# Vending.net
KiCad netlist of a schematic drawn in EAGLE
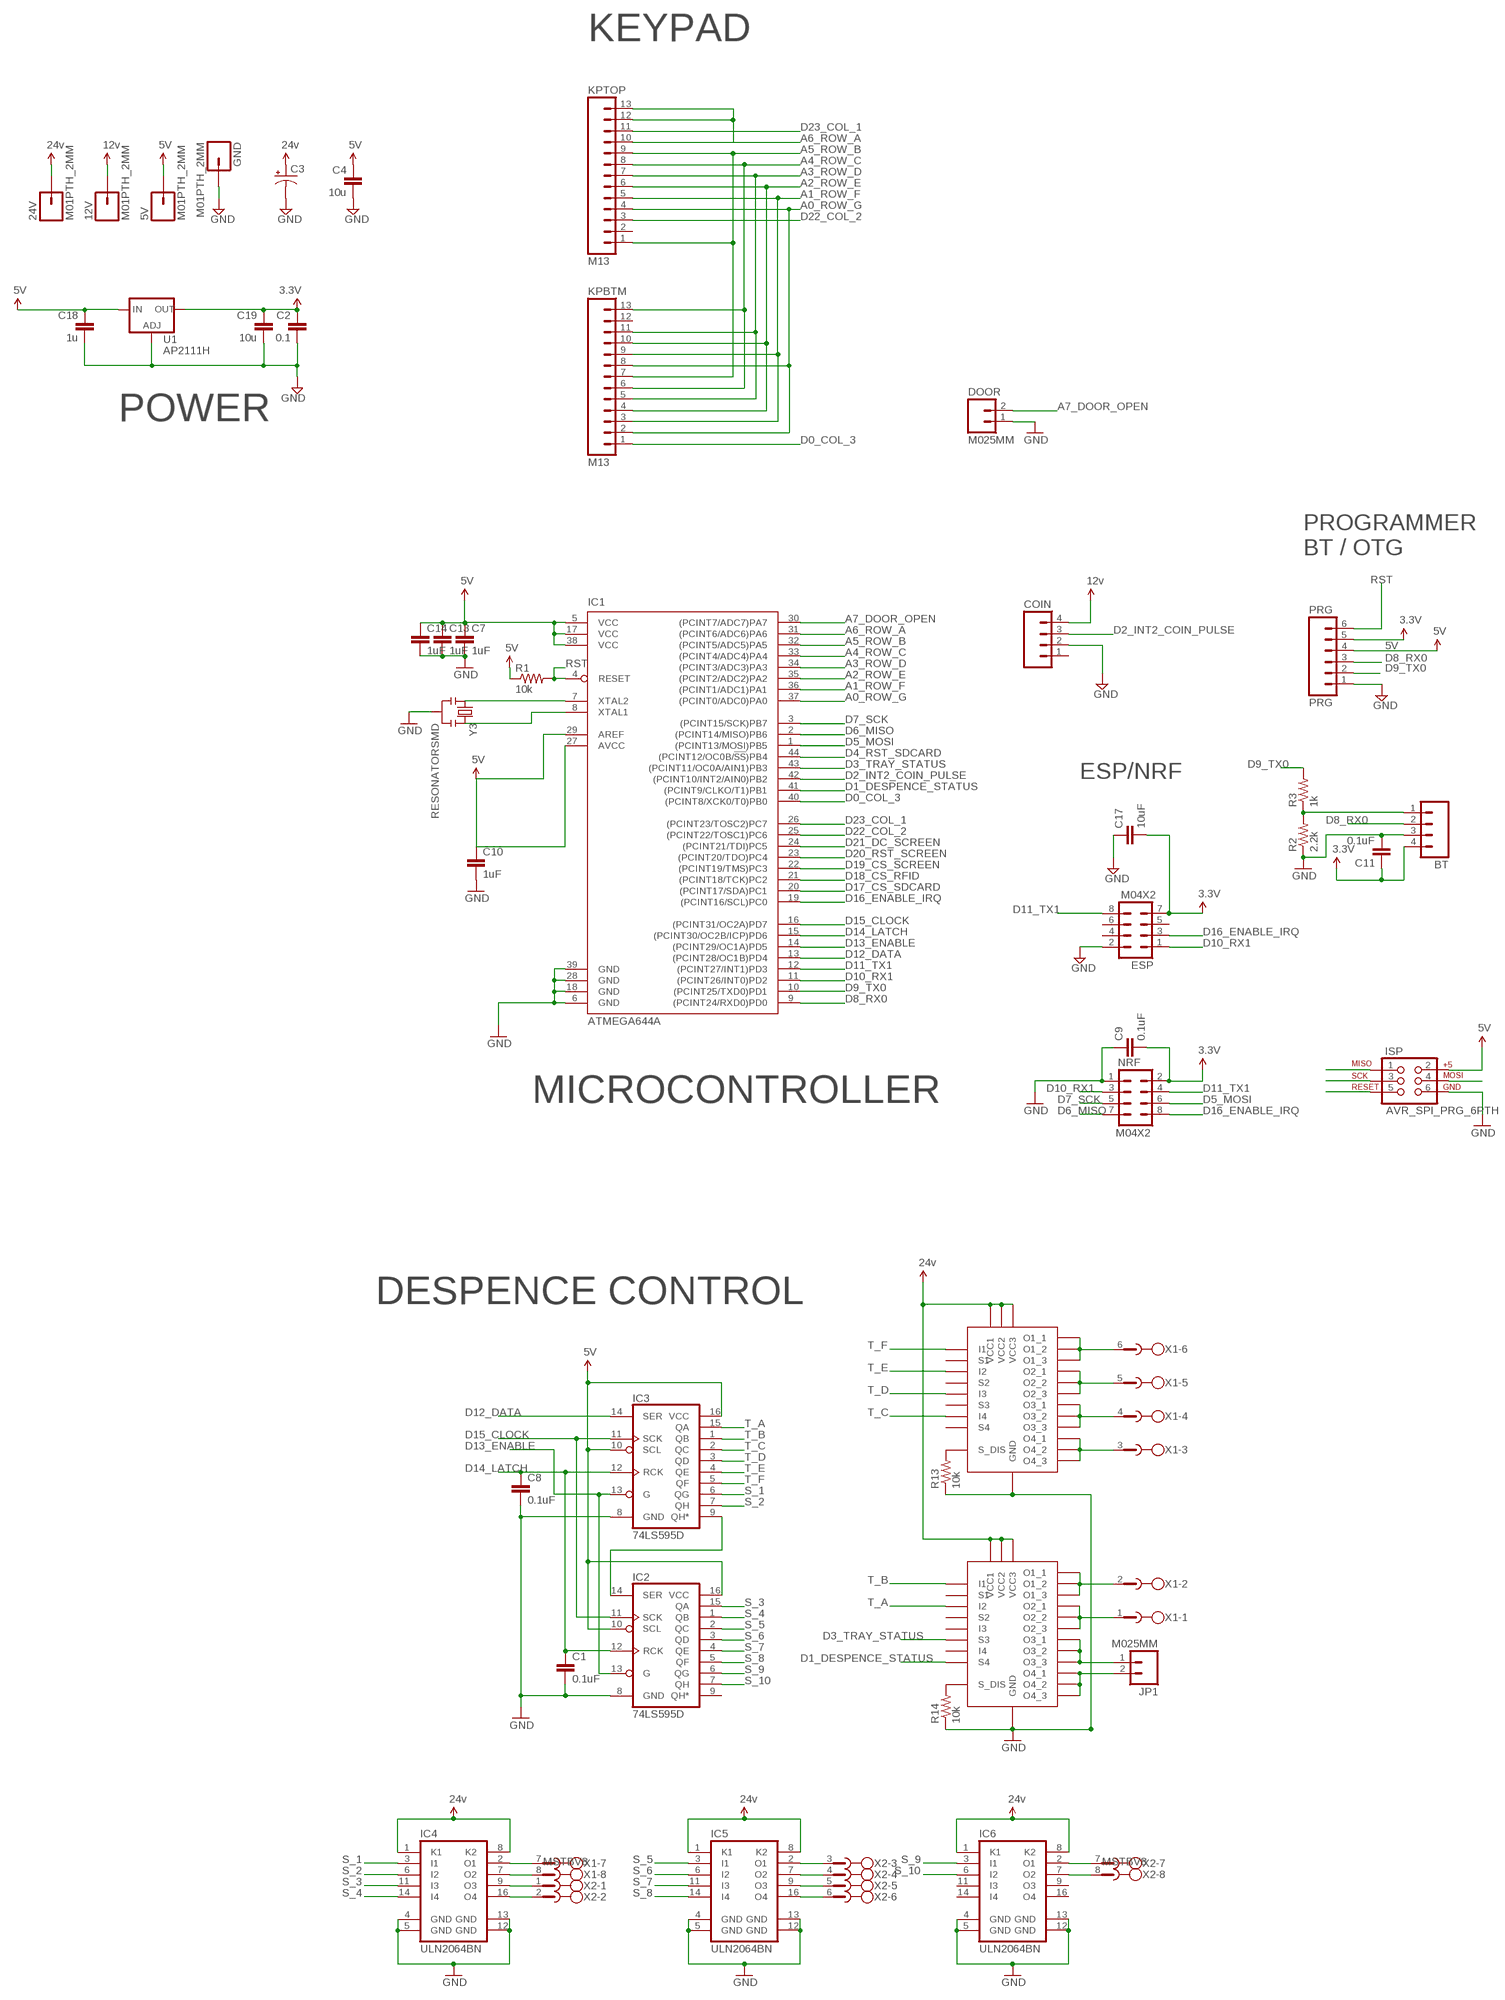
[diagram p0: schematic, sheet 1, part 1 of 2]
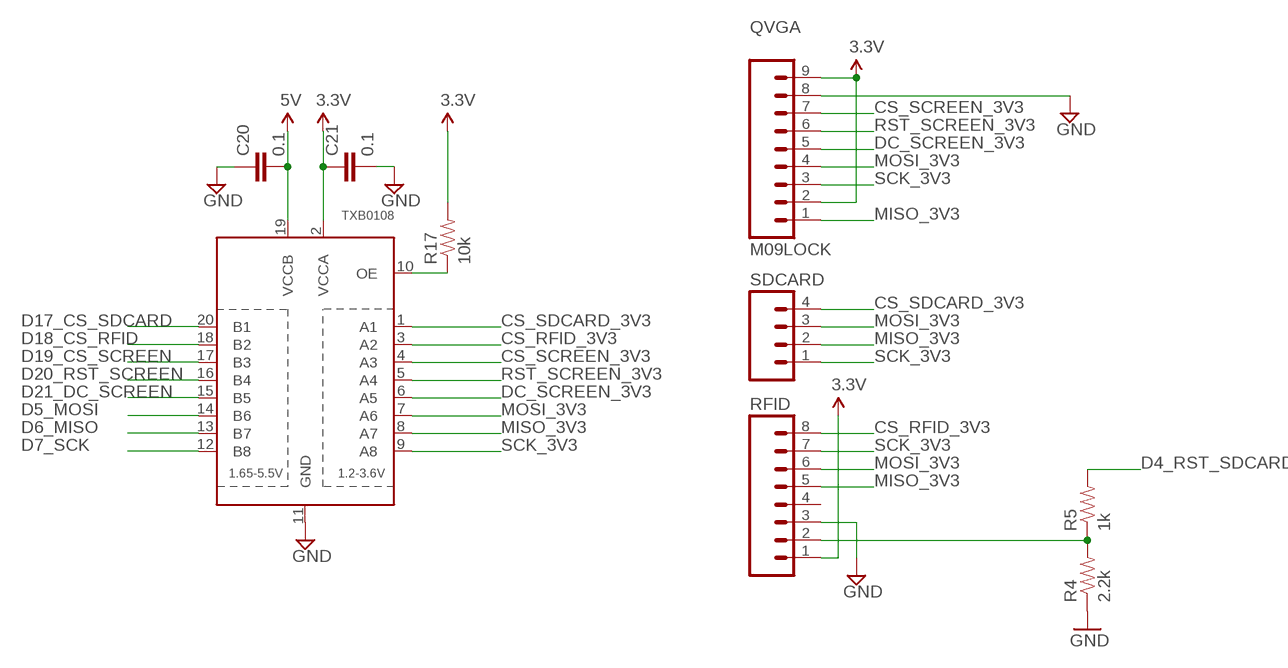
[diagram p1: schematic, sheet 1, part 2 of 2]

(export (version "E")
  (design (tool "Eeschema 10.0.6"))
  (components
    (comp (ref "5V")
      (value "M01PTH_2MM")
      (footprint "eagle-import:1X01_2MM")
      (libsource (lib "eagle-import") (part "M01PTH_2MM"))
    )
    (comp (ref "12V")
      (value "M01PTH_2MM")
      (footprint "eagle-import:1X01_2MM")
      (libsource (lib "eagle-import") (part "M01PTH_2MM"))
    )
    (comp (ref "24V")
      (value "M01PTH_2MM")
      (footprint "eagle-import:1X01_2MM")
      (libsource (lib "eagle-import") (part "M01PTH_2MM"))
    )
    (comp (ref "BT")
      (value "M04PTH")
      (footprint "eagle-import:1X04")
      (libsource (lib "eagle-import") (part "M04PTH"))
    )
    (comp (ref "C1")
      (value "0.1uF")
      (footprint "eagle-import:0805")
      (libsource (lib "eagle-import") (part "SparkFun-Capacitors_CAP0805"))
    )
    (comp (ref "C2")
      (value "0.1")
      (footprint "eagle-import:0805")
      (libsource (lib "eagle-import") (part "CAP0805"))
    )
    (comp (ref "C3")
      (value "CAP_POLPTH4")
      (footprint "eagle-import:CPOL-RADIAL-1000UF-25V")
      (libsource (lib "eagle-import") (part "CAP_POLPTH4"))
    )
    (comp (ref "C4")
      (value "10u")
      (footprint "eagle-import:0805-CAP")
      (libsource (lib "eagle-import") (part "CAP0805-CAP"))
    )
    (comp (ref "C7")
      (value "1uF")
      (footprint "eagle-import:0805")
      (libsource (lib "eagle-import") (part "SparkFun-Capacitors_CAP0805"))
    )
    (comp (ref "C8")
      (value "0.1uF")
      (footprint "eagle-import:0805")
      (libsource (lib "eagle-import") (part "SparkFun-Capacitors_CAP0805"))
    )
    (comp (ref "C9")
      (value "0.1uF")
      (footprint "eagle-import:0805")
      (libsource (lib "eagle-import") (part "SparkFun-Capacitors_CAP0805"))
    )
    (comp (ref "C10")
      (value "1uF")
      (footprint "eagle-import:0805")
      (libsource (lib "eagle-import") (part "SparkFun-Capacitors_CAP0805"))
    )
    (comp (ref "C11")
      (value "0.1uF")
      (footprint "eagle-import:0805")
      (libsource (lib "eagle-import") (part "SparkFun-Capacitors_CAP0805"))
    )
    (comp (ref "C13")
      (value "1uF")
      (footprint "eagle-import:0805")
      (libsource (lib "eagle-import") (part "SparkFun-Capacitors_CAP0805"))
    )
    (comp (ref "C14")
      (value "1uF")
      (footprint "eagle-import:0805")
      (libsource (lib "eagle-import") (part "SparkFun-Capacitors_CAP0805"))
    )
    (comp (ref "C17")
      (value "10uF")
      (footprint "eagle-import:0805")
      (libsource (lib "eagle-import") (part "SparkFun-Capacitors_CAP0805"))
    )
    (comp (ref "C18")
      (value "1u")
      (footprint "eagle-import:0805")
      (libsource (lib "eagle-import") (part "CAP0805"))
    )
    (comp (ref "C19")
      (value "10u")
      (footprint "eagle-import:0805-CAP")
      (libsource (lib "eagle-import") (part "CAP0805-CAP"))
    )
    (comp (ref "C20")
      (value "0.1")
      (footprint "eagle-import:0805")
      (libsource (lib "eagle-import") (part "CAP0805"))
    )
    (comp (ref "C21")
      (value "0.1")
      (footprint "eagle-import:0805")
      (libsource (lib "eagle-import") (part "CAP0805"))
    )
    (comp (ref "COIN")
      (value "M04PTH")
      (footprint "eagle-import:1X04")
      (libsource (lib "eagle-import") (part "M04PTH"))
    )
    (comp (ref "DOOR")
      (value "M025MM")
      (footprint "eagle-import:SCREWTERMINAL-5MM-2")
      (libsource (lib "eagle-import") (part "M025MM"))
    )
    (comp (ref "ESP")
      (value "M04X2")
      (footprint "eagle-import:2X4")
      (libsource (lib "eagle-import") (part "M04X2"))
    )
    (comp (ref "GND")
      (value "M01PTH_2MM")
      (footprint "eagle-import:1X01_2MM")
      (libsource (lib "eagle-import") (part "M01PTH_2MM"))
    )
    (comp (ref "IC1")
      (value "ATMEGA644A")
      (footprint "eagle-import:TQFP44")
      (fields (field (name "MPN") "ATMEGA644PV-10AU"))
      (libsource (lib "eagle-import") (part "ATMEGA644A"))
    )
    (comp (ref "IC2")
      (value "74LS595D")
      (footprint "eagle-import:SO16")
      (libsource (lib "eagle-import") (part "74595DLS"))
    )
    (comp (ref "IC3")
      (value "74LS595D")
      (footprint "eagle-import:SO16")
      (libsource (lib "eagle-import") (part "74595DLS"))
    )
    (comp (ref "IC4")
      (value "ULN2064BN")
      (footprint "eagle-import:DIL16")
      (libsource (lib "eagle-import") (part "ULN2064BN"))
    )
    (comp (ref "IC5")
      (value "ULN2064BN")
      (footprint "eagle-import:DIL16")
      (libsource (lib "eagle-import") (part "ULN2064BN"))
    )
    (comp (ref "IC6")
      (value "ULN2064BN")
      (footprint "eagle-import:DIL16")
      (libsource (lib "eagle-import") (part "ULN2064BN"))
    )
    (comp (ref "ISP")
      (value "AVR_SPI_PRG_6PTH")
      (footprint "eagle-import:2X3")
      (libsource (lib "eagle-import") (part "AVR_SPI_PRG_6PTH"))
    )
    (comp (ref "JP1")
      (value "M025MM")
      (footprint "eagle-import:SCREWTERMINAL-5MM-2")
      (libsource (lib "eagle-import") (part "M025MM"))
    )
    (comp (ref "KPBTM")
      (value "M13")
      (footprint "eagle-import:1X13")
      (libsource (lib "eagle-import") (part "M13"))
    )
    (comp (ref "KPTOP")
      (value "M13")
      (footprint "eagle-import:1X13")
      (libsource (lib "eagle-import") (part "M13"))
    )
    (comp (ref "NRF")
      (value "M04X2")
      (footprint "eagle-import:2X4")
      (libsource (lib "eagle-import") (part "M04X2"))
    )
    (comp (ref "PRG")
      (value "PRG")
      (footprint "eagle-import:1X06")
      (libsource (lib "eagle-import") (part "M06SIP"))
    )
    (comp (ref "QVGA")
      (value "M09LOCK")
      (footprint "eagle-import:1X09_LOCK")
      (libsource (lib "eagle-import") (part "M09LOCK"))
    )
    (comp (ref "R1")
      (value "10k")
      (footprint "eagle-import:0805")
      (libsource (lib "eagle-import") (part "RESISTOR0805-RES"))
    )
    (comp (ref "R2")
      (value "2.2k")
      (footprint "eagle-import:0805")
      (libsource (lib "eagle-import") (part "RESISTOR0805-RES"))
    )
    (comp (ref "R3")
      (value "1k")
      (footprint "eagle-import:0805")
      (libsource (lib "eagle-import") (part "RESISTOR0805-RES"))
    )
    (comp (ref "R4")
      (value "2.2k")
      (footprint "eagle-import:0805")
      (libsource (lib "eagle-import") (part "RESISTOR0805-RES"))
    )
    (comp (ref "R5")
      (value "1k")
      (footprint "eagle-import:0805")
      (libsource (lib "eagle-import") (part "RESISTOR0805-RES"))
    )
    (comp (ref "R13")
      (value "10k")
      (footprint "eagle-import:0805")
      (libsource (lib "eagle-import") (part "RESISTOR0805-RES"))
    )
    (comp (ref "R14")
      (value "10k")
      (footprint "eagle-import:0805")
      (libsource (lib "eagle-import") (part "RESISTOR0805-RES"))
    )
    (comp (ref "R17")
      (value "10k")
      (footprint "eagle-import:0805")
      (libsource (lib "eagle-import") (part "RESISTOR0805-RES"))
    )
    (comp (ref "RFID")
      (value "M08LOCK")
      (footprint "eagle-import:1X08_LOCK")
      (libsource (lib "eagle-import") (part "M08LOCK"))
    )
    (comp (ref "SDCARD")
      (value "M04LOCK")
      (footprint "eagle-import:1X04_LOCK")
      (libsource (lib "eagle-import") (part "M04LOCK"))
    )
    (comp (ref "TXB0108")
      (value "TXB0108PWR")
      (footprint "eagle-import:TSSOP20")
      (libsource (lib "eagle-import") (part "TXB0108PWR"))
    )
    (comp (ref "U$2")
      (value "VNQ5E160K-E")
      (footprint "eagle-import:POWERS0-24")
      (libsource (lib "eagle-import") (part "VNQ5E160K-E"))
    )
    (comp (ref "U$3")
      (value "VNQ5E160K-E")
      (footprint "eagle-import:POWERS0-24")
      (libsource (lib "eagle-import") (part "VNQ5E160K-E"))
    )
    (comp (ref "U1")
      (value "AP2111H")
      (footprint "eagle-import:SOT223")
      (libsource (lib "eagle-import") (part "V_REG_317SMD"))
    )
    (comp (ref "X1")
      (value "MSTBV8")
      (footprint "eagle-import:MSTBV8")
      (fields (field (name "MPN") "MSTBV 2,5/8-GF-5.08"))
      (libsource (lib "eagle-import") (part "MSTBV8"))
    )
    (comp (ref "X2")
      (value "MSTBV8")
      (footprint "eagle-import:MSTBV8")
      (fields
        (field (name "MPN") "MSTBV 2,5/8-GF-5.08")
        (field (name "MPN_1") "MSTBV 2,5/8-GF-5.08")
        (field (name "OC_FARNELL") "1792797")
        (field (name "OC_NEWARK") "69R9850")
      )
      (libsource (lib "eagle-import") (part "MSTBV8"))
    )
    (comp (ref "Y3")
      (value "RESONATORSMD")
      (footprint "eagle-import:RESONATOR-SMD")
      (libsource (lib "eagle-import") (part "RESONATORSMD"))
    )
  )
  (nets
    (net (code "1") (name "/A0_ROW_G") (class "Default")
      (node (ref "IC1") (pin "37") (pinfunction "(PCINT0/ADC0)PA0_37") (pintype "bidirectional"))
      (node (ref "KPBTM") (pin "2") (pinfunction "2_2") (pintype "passive"))
      (node (ref "KPBTM") (pin "8") (pinfunction "8_8") (pintype "passive"))
      (node (ref "KPTOP") (pin "4") (pinfunction "4_4") (pintype "passive"))
    )
    (net (code "2") (name "/A1_ROW_F") (class "Default")
      (node (ref "IC1") (pin "36") (pinfunction "(PCINT1/ADC1)PA1_36") (pintype "bidirectional"))
      (node (ref "KPBTM") (pin "3") (pinfunction "3_3") (pintype "passive"))
      (node (ref "KPBTM") (pin "9") (pinfunction "9_9") (pintype "passive"))
      (node (ref "KPTOP") (pin "5") (pinfunction "5_5") (pintype "passive"))
    )
    (net (code "3") (name "/A2_ROW_E") (class "Default")
      (node (ref "IC1") (pin "35") (pinfunction "(PCINT2/ADC2)PA2_35") (pintype "bidirectional"))
      (node (ref "KPBTM") (pin "10") (pinfunction "10_10") (pintype "passive"))
      (node (ref "KPBTM") (pin "4") (pinfunction "4_4") (pintype "passive"))
      (node (ref "KPTOP") (pin "6") (pinfunction "6_6") (pintype "passive"))
    )
    (net (code "4") (name "/A3_ROW_D") (class "Default")
      (node (ref "IC1") (pin "34") (pinfunction "(PCINT3/ADC3)PA3_34") (pintype "bidirectional"))
      (node (ref "KPBTM") (pin "11") (pinfunction "11_11") (pintype "passive"))
      (node (ref "KPBTM") (pin "5") (pinfunction "5_5") (pintype "passive"))
      (node (ref "KPTOP") (pin "7") (pinfunction "7_7") (pintype "passive"))
    )
    (net (code "5") (name "/A4_ROW_C") (class "Default")
      (node (ref "IC1") (pin "33") (pinfunction "(PCINT4/ADC4)PA4_33") (pintype "bidirectional"))
      (node (ref "KPBTM") (pin "13") (pinfunction "13_13") (pintype "passive"))
      (node (ref "KPBTM") (pin "6") (pinfunction "6_6") (pintype "passive"))
      (node (ref "KPTOP") (pin "8") (pinfunction "8_8") (pintype "passive"))
    )
    (net (code "6") (name "/A5_ROW_B") (class "Default")
      (node (ref "IC1") (pin "32") (pinfunction "(PCINT5/ADC5)PA5_32") (pintype "bidirectional"))
      (node (ref "KPBTM") (pin "7") (pinfunction "7_7") (pintype "passive"))
      (node (ref "KPTOP") (pin "1") (pinfunction "1_1") (pintype "passive"))
      (node (ref "KPTOP") (pin "9") (pinfunction "9_9") (pintype "passive"))
    )
    (net (code "7") (name "/A6_ROW_A") (class "Default")
      (node (ref "IC1") (pin "31") (pinfunction "(PCINT6/ADC6)PA6_31") (pintype "bidirectional"))
      (node (ref "KPTOP") (pin "10") (pinfunction "10_10") (pintype "passive"))
      (node (ref "KPTOP") (pin "12") (pinfunction "12_12") (pintype "passive"))
      (node (ref "KPTOP") (pin "13") (pinfunction "13_13") (pintype "passive"))
    )
    (net (code "8") (name "/A7_DOOR_OPEN") (class "Default")
      (node (ref "DOOR") (pin "2") (pinfunction "2_2") (pintype "passive"))
      (node (ref "IC1") (pin "30") (pinfunction "(PCINT7/ADC7)PA7_30") (pintype "bidirectional"))
    )
    (net (code "9") (name "/CS_RFID_3V3") (class "Default")
      (node (ref "RFID") (pin "8") (pinfunction "8_8") (pintype "passive"))
      (node (ref "TXB0108") (pin "3") (pinfunction "A2_3") (pintype "bidirectional"))
    )
    (net (code "10") (name "/CS_SCREEN_3V3") (class "Default")
      (node (ref "QVGA") (pin "7") (pinfunction "7_7") (pintype "passive"))
      (node (ref "TXB0108") (pin "4") (pinfunction "A3_4") (pintype "bidirectional"))
    )
    (net (code "11") (name "/CS_SDCARD_3V3") (class "Default")
      (node (ref "SDCARD") (pin "4") (pinfunction "4_4") (pintype "passive"))
      (node (ref "TXB0108") (pin "1") (pinfunction "A1_1") (pintype "bidirectional"))
    )
    (net (code "12") (name "/D0_COL_3") (class "Default")
      (node (ref "IC1") (pin "40") (pinfunction "(PCINT8/XCK0/T0)PB0_40") (pintype "bidirectional"))
      (node (ref "KPBTM") (pin "1") (pinfunction "1_1") (pintype "passive"))
    )
    (net (code "13") (name "/D1_DESPENCE_STATUS") (class "Default")
      (node (ref "IC1") (pin "41") (pinfunction "(PCINT9/CLKO/T1)PB1_41") (pintype "bidirectional"))
      (node (ref "U$3") (pin "10") (pinfunction "S4_10") (pintype "bidirectional"))
    )
    (net (code "14") (name "/D2_INT2_COIN_PULSE") (class "Default")
      (node (ref "COIN") (pin "3") (pinfunction "3_3") (pintype "passive"))
      (node (ref "IC1") (pin "42") (pinfunction "(PCINT10/INT2/AIN0)PB2_42") (pintype "bidirectional"))
    )
    (net (code "15") (name "/D3_TRAY_STATUS") (class "Default")
      (node (ref "IC1") (pin "43") (pinfunction "(PCINT11/OC0A/AIN1)PB3_43") (pintype "bidirectional"))
      (node (ref "U$3") (pin "8") (pinfunction "S3_8") (pintype "bidirectional"))
    )
    (net (code "16") (name "/D4_RST_SDCARD") (class "Default")
      (node (ref "IC1") (pin "44") (pinfunction "(PCINT12/OC0B/~{SS})PB4_44") (pintype "bidirectional"))
      (node (ref "R5") (pin "2") (pinfunction "2_2") (pintype "passive"))
    )
    (net (code "17") (name "/D5_MOSI") (class "Default")
      (node (ref "IC1") (pin "1") (pinfunction "(PCINT13/MOSI)PB5_1") (pintype "bidirectional"))
      (node (ref "ISP") (pin "4") (pinfunction "4_4") (pintype "passive"))
      (node (ref "NRF") (pin "6") (pinfunction "6_6") (pintype "passive"))
      (node (ref "TXB0108") (pin "14") (pinfunction "B6_14") (pintype "bidirectional"))
    )
    (net (code "18") (name "/D6_MISO") (class "Default")
      (node (ref "IC1") (pin "2") (pinfunction "(PCINT14/MISO)PB6_2") (pintype "bidirectional"))
      (node (ref "ISP") (pin "1") (pinfunction "1_1") (pintype "passive"))
      (node (ref "NRF") (pin "7") (pinfunction "7_7") (pintype "passive"))
      (node (ref "TXB0108") (pin "13") (pinfunction "B7_13") (pintype "bidirectional"))
    )
    (net (code "19") (name "/D7_SCK") (class "Default")
      (node (ref "IC1") (pin "3") (pinfunction "(PCINT15/SCK)PB7_3") (pintype "bidirectional"))
      (node (ref "ISP") (pin "3") (pinfunction "3_3") (pintype "passive"))
      (node (ref "NRF") (pin "5") (pinfunction "5_5") (pintype "passive"))
      (node (ref "TXB0108") (pin "12") (pinfunction "B8_12") (pintype "bidirectional"))
    )
    (net (code "20") (name "/D8_RX0") (class "Default")
      (node (ref "BT") (pin "2") (pinfunction "2_2") (pintype "passive"))
      (node (ref "IC1") (pin "9") (pinfunction "(PCINT24/RXD0)PD0_9") (pintype "bidirectional"))
      (node (ref "PRG") (pin "3") (pinfunction "3_3") (pintype "passive"))
    )
    (net (code "21") (name "/D9_TX0") (class "Default")
      (node (ref "IC1") (pin "10") (pinfunction "(PCINT25/TXD0)PD1_10") (pintype "bidirectional"))
      (node (ref "PRG") (pin "2") (pinfunction "2_2") (pintype "passive"))
      (node (ref "R3") (pin "2") (pinfunction "2_2") (pintype "passive"))
    )
    (net (code "22") (name "/D10_RX1") (class "Default")
      (node (ref "ESP") (pin "1") (pinfunction "1_1") (pintype "passive"))
      (node (ref "IC1") (pin "11") (pinfunction "(PCINT26/INT0)PD2_11") (pintype "bidirectional"))
      (node (ref "NRF") (pin "3") (pinfunction "3_3") (pintype "passive"))
    )
    (net (code "23") (name "/D11_TX1") (class "Default")
      (node (ref "ESP") (pin "8") (pinfunction "8_8") (pintype "passive"))
      (node (ref "IC1") (pin "12") (pinfunction "(PCINT27/INT1)PD3_12") (pintype "bidirectional"))
      (node (ref "NRF") (pin "4") (pinfunction "4_4") (pintype "passive"))
    )
    (net (code "24") (name "/D12_DATA") (class "Default")
      (node (ref "IC1") (pin "13") (pinfunction "(PCINT28/OC1B)PD4_13") (pintype "bidirectional"))
      (node (ref "IC3") (pin "14") (pinfunction "SER_14") (pintype "input"))
    )
    (net (code "25") (name "/D13_ENABLE") (class "Default")
      (node (ref "IC1") (pin "14") (pinfunction "(PCINT29/OC1A)PD5_14") (pintype "bidirectional"))
      (node (ref "IC2") (pin "13") (pinfunction "G_13") (pintype "input"))
      (node (ref "IC3") (pin "13") (pinfunction "G_13") (pintype "input"))
    )
    (net (code "26") (name "/D14_LATCH") (class "Default")
      (node (ref "C1") (pin "1") (pinfunction "1_1") (pintype "passive"))
      (node (ref "C8") (pin "1") (pinfunction "1_1") (pintype "passive"))
      (node (ref "IC1") (pin "15") (pinfunction "(PCINT30/OC2B/ICP)PD6_15") (pintype "bidirectional"))
      (node (ref "IC2") (pin "12") (pinfunction "RCK_12") (pintype "input"))
      (node (ref "IC3") (pin "12") (pinfunction "RCK_12") (pintype "input"))
    )
    (net (code "27") (name "/D15_CLOCK") (class "Default")
      (node (ref "IC1") (pin "16") (pinfunction "(PCINT31/OC2A)PD7_16") (pintype "bidirectional"))
      (node (ref "IC2") (pin "11") (pinfunction "SCK_11") (pintype "input"))
      (node (ref "IC3") (pin "11") (pinfunction "SCK_11") (pintype "input"))
    )
    (net (code "28") (name "/D16_ENABLE_IRQ") (class "Default")
      (node (ref "ESP") (pin "3") (pinfunction "3_3") (pintype "passive"))
      (node (ref "IC1") (pin "19") (pinfunction "(PCINT16/SCL)PC0_19") (pintype "output"))
      (node (ref "NRF") (pin "8") (pinfunction "8_8") (pintype "passive"))
    )
    (net (code "29") (name "/D17_CS_SDCARD") (class "Default")
      (node (ref "IC1") (pin "20") (pinfunction "(PCINT17/SDA)PC1_20") (pintype "output"))
      (node (ref "TXB0108") (pin "20") (pinfunction "B1_20") (pintype "bidirectional"))
    )
    (net (code "30") (name "/D18_CS_RFID") (class "Default")
      (node (ref "IC1") (pin "21") (pinfunction "(PCINT18/TCK)PC2_21") (pintype "output"))
      (node (ref "TXB0108") (pin "18") (pinfunction "B2_18") (pintype "bidirectional"))
    )
    (net (code "31") (name "/D19_CS_SCREEN") (class "Default")
      (node (ref "IC1") (pin "22") (pinfunction "(PCINT19/TMS)PC3_22") (pintype "output"))
      (node (ref "TXB0108") (pin "17") (pinfunction "B3_17") (pintype "bidirectional"))
    )
    (net (code "32") (name "/D20_RST_SCREEN") (class "Default")
      (node (ref "IC1") (pin "23") (pinfunction "(PCINT20/TDO)PC4_23") (pintype "output"))
      (node (ref "TXB0108") (pin "16") (pinfunction "B4_16") (pintype "bidirectional"))
    )
    (net (code "33") (name "/D21_DC_SCREEN") (class "Default")
      (node (ref "IC1") (pin "24") (pinfunction "(PCINT21/TDI)PC5_24") (pintype "output"))
      (node (ref "TXB0108") (pin "15") (pinfunction "B5_15") (pintype "bidirectional"))
    )
    (net (code "34") (name "/D22_COL_2") (class "Default")
      (node (ref "IC1") (pin "25") (pinfunction "(PCINT22/TOSC1)PC6_25") (pintype "output"))
      (node (ref "KPTOP") (pin "3") (pinfunction "3_3") (pintype "passive"))
    )
    (net (code "35") (name "/D23_COL_1") (class "Default")
      (node (ref "IC1") (pin "26") (pinfunction "(PCINT23/TOSC2)PC7_26") (pintype "output"))
      (node (ref "KPTOP") (pin "11") (pinfunction "11_11") (pintype "passive"))
    )
    (net (code "36") (name "/DC_SCREEN_3V3") (class "Default")
      (node (ref "QVGA") (pin "5") (pinfunction "5_5") (pintype "passive"))
      (node (ref "TXB0108") (pin "6") (pinfunction "A5_6") (pintype "bidirectional"))
    )
    (net (code "37") (name "/MISO_3V3") (class "Default")
      (node (ref "QVGA") (pin "1") (pinfunction "1_1") (pintype "passive"))
      (node (ref "RFID") (pin "5") (pinfunction "5_5") (pintype "passive"))
      (node (ref "SDCARD") (pin "2") (pinfunction "2_2") (pintype "passive"))
      (node (ref "TXB0108") (pin "8") (pinfunction "A7_8") (pintype "bidirectional"))
    )
    (net (code "38") (name "/MOSI_3V3") (class "Default")
      (node (ref "QVGA") (pin "4") (pinfunction "4_4") (pintype "passive"))
      (node (ref "RFID") (pin "6") (pinfunction "6_6") (pintype "passive"))
      (node (ref "SDCARD") (pin "3") (pinfunction "3_3") (pintype "passive"))
      (node (ref "TXB0108") (pin "7") (pinfunction "A6_7") (pintype "bidirectional"))
    )
    (net (code "39") (name "/RST") (class "Default")
      (node (ref "IC1") (pin "4") (pinfunction "RESET_4") (pintype "input"))
      (node (ref "ISP") (pin "5") (pinfunction "5_5") (pintype "passive"))
      (node (ref "PRG") (pin "6") (pinfunction "6_6") (pintype "passive"))
      (node (ref "R1") (pin "2") (pinfunction "2_2") (pintype "passive"))
    )
    (net (code "40") (name "/RST_SCREEN_3V3") (class "Default")
      (node (ref "QVGA") (pin "6") (pinfunction "6_6") (pintype "passive"))
      (node (ref "TXB0108") (pin "5") (pinfunction "A4_5") (pintype "bidirectional"))
    )
    (net (code "41") (name "/SCK_3V3") (class "Default")
      (node (ref "QVGA") (pin "3") (pinfunction "3_3") (pintype "passive"))
      (node (ref "RFID") (pin "7") (pinfunction "7_7") (pintype "passive"))
      (node (ref "SDCARD") (pin "1") (pinfunction "1_1") (pintype "passive"))
      (node (ref "TXB0108") (pin "9") (pinfunction "A8_9") (pintype "bidirectional"))
    )
    (net (code "42") (name "/S_1") (class "Default")
      (node (ref "IC3") (pin "6") (pinfunction "QG_6") (pintype "tri_state"))
      (node (ref "IC4") (pin "3") (pinfunction "I1_3") (pintype "input"))
    )
    (net (code "43") (name "/S_2") (class "Default")
      (node (ref "IC3") (pin "7") (pinfunction "QH_7") (pintype "tri_state"))
      (node (ref "IC4") (pin "6") (pinfunction "I2_6") (pintype "input"))
    )
    (net (code "44") (name "/S_3") (class "Default")
      (node (ref "IC2") (pin "15") (pinfunction "QA_15") (pintype "tri_state"))
      (node (ref "IC4") (pin "11") (pinfunction "I3_11") (pintype "input"))
    )
    (net (code "45") (name "/S_4") (class "Default")
      (node (ref "IC2") (pin "1") (pinfunction "QB_1") (pintype "tri_state"))
      (node (ref "IC4") (pin "14") (pinfunction "I4_14") (pintype "input"))
    )
    (net (code "46") (name "/S_5") (class "Default")
      (node (ref "IC2") (pin "2") (pinfunction "QC_2") (pintype "tri_state"))
      (node (ref "IC5") (pin "3") (pinfunction "I1_3") (pintype "input"))
    )
    (net (code "47") (name "/S_6") (class "Default")
      (node (ref "IC2") (pin "3") (pinfunction "QD_3") (pintype "tri_state"))
      (node (ref "IC5") (pin "6") (pinfunction "I2_6") (pintype "input"))
    )
    (net (code "48") (name "/S_7") (class "Default")
      (node (ref "IC2") (pin "4") (pinfunction "QE_4") (pintype "tri_state"))
      (node (ref "IC5") (pin "11") (pinfunction "I3_11") (pintype "input"))
    )
    (net (code "49") (name "/S_8") (class "Default")
      (node (ref "IC2") (pin "5") (pinfunction "QF_5") (pintype "tri_state"))
      (node (ref "IC5") (pin "14") (pinfunction "I4_14") (pintype "input"))
    )
    (net (code "50") (name "/S_9") (class "Default")
      (node (ref "IC2") (pin "6") (pinfunction "QG_6") (pintype "tri_state"))
      (node (ref "IC6") (pin "3") (pinfunction "I1_3") (pintype "input"))
    )
    (net (code "51") (name "/S_10") (class "Default")
      (node (ref "IC2") (pin "7") (pinfunction "QH_7") (pintype "tri_state"))
      (node (ref "IC6") (pin "6") (pinfunction "I2_6") (pintype "input"))
    )
    (net (code "52") (name "/T_A") (class "Default")
      (node (ref "IC3") (pin "15") (pinfunction "QA_15") (pintype "tri_state"))
      (node (ref "U$3") (pin "5") (pinfunction "I2_5") (pintype "bidirectional"))
    )
    (net (code "53") (name "/T_B") (class "Default")
      (node (ref "IC3") (pin "1") (pinfunction "QB_1") (pintype "tri_state"))
      (node (ref "U$3") (pin "3") (pinfunction "I1_3") (pintype "bidirectional"))
    )
    (net (code "54") (name "/T_C") (class "Default")
      (node (ref "IC3") (pin "2") (pinfunction "QC_2") (pintype "tri_state"))
      (node (ref "U$2") (pin "9") (pinfunction "I4_9") (pintype "bidirectional"))
    )
    (net (code "55") (name "/T_D") (class "Default")
      (node (ref "IC3") (pin "3") (pinfunction "QD_3") (pintype "tri_state"))
      (node (ref "U$2") (pin "7") (pinfunction "I3_7") (pintype "bidirectional"))
    )
    (net (code "56") (name "/T_E") (class "Default")
      (node (ref "IC3") (pin "4") (pinfunction "QE_4") (pintype "tri_state"))
      (node (ref "U$2") (pin "5") (pinfunction "I2_5") (pintype "bidirectional"))
    )
    (net (code "57") (name "/T_F") (class "Default")
      (node (ref "IC3") (pin "5") (pinfunction "QF_5") (pintype "tri_state"))
      (node (ref "U$2") (pin "3") (pinfunction "I1_3") (pintype "bidirectional"))
    )
    (net (code "58") (name "3.3V") (class "Default")
      (node (ref "BT") (pin "4") (pinfunction "4_4") (pintype "passive"))
      (node (ref "C11") (pin "1") (pinfunction "1_1") (pintype "passive"))
      (node (ref "C17") (pin "2") (pinfunction "2_2") (pintype "passive"))
      (node (ref "C19") (pin "1") (pinfunction "1_1") (pintype "passive"))
      (node (ref "C2") (pin "1") (pinfunction "1_1") (pintype "passive"))
      (node (ref "C21") (pin "1") (pinfunction "1_1") (pintype "passive"))
      (node (ref "C9") (pin "2") (pinfunction "2_2") (pintype "passive"))
      (node (ref "ESP") (pin "7") (pinfunction "7_7") (pintype "passive"))
      (node (ref "NRF") (pin "2") (pinfunction "2_2") (pintype "passive"))
      (node (ref "PRG") (pin "5") (pinfunction "5_5") (pintype "passive"))
      (node (ref "QVGA") (pin "2") (pinfunction "2_2") (pintype "passive"))
      (node (ref "QVGA") (pin "9") (pinfunction "9_9") (pintype "passive"))
      (node (ref "R17") (pin "2") (pinfunction "2_2") (pintype "passive"))
      (node (ref "RFID") (pin "1") (pinfunction "1_1") (pintype "passive"))
      (node (ref "TXB0108") (pin "2") (pinfunction "VCCA_2") (pintype "bidirectional"))
      (node (ref "U1") (pin "2") (pinfunction "OUT_2") (pintype "output"))
    )
    (net (code "59") (name "5V") (class "Default")
      (node (ref "5V") (pin "1") (pinfunction "1_1") (pintype "passive"))
      (node (ref "C10") (pin "1") (pinfunction "1_1") (pintype "passive"))
      (node (ref "C13") (pin "1") (pinfunction "1_1") (pintype "passive"))
      (node (ref "C14") (pin "1") (pinfunction "1_1") (pintype "passive"))
      (node (ref "C18") (pin "1") (pinfunction "1_1") (pintype "passive"))
      (node (ref "C20") (pin "2") (pinfunction "2_2") (pintype "passive"))
      (node (ref "C4") (pin "1") (pinfunction "1_1") (pintype "passive"))
      (node (ref "C7") (pin "1") (pinfunction "1_1") (pintype "passive"))
      (node (ref "IC1") (pin "17") (pinfunction "VCC_17") (pintype "power_in"))
      (node (ref "IC1") (pin "27") (pinfunction "AVCC_27") (pintype "power_in"))
      (node (ref "IC1") (pin "29") (pinfunction "AREF_29") (pintype "passive"))
      (node (ref "IC1") (pin "38") (pinfunction "VCC_38") (pintype "power_in"))
      (node (ref "IC1") (pin "5") (pinfunction "VCC_5") (pintype "power_in"))
      (node (ref "IC2") (pin "10") (pinfunction "SCL_10") (pintype "input"))
      (node (ref "IC2") (pin "16") (pinfunction "VCC_16") (pintype "power_in"))
      (node (ref "IC3") (pin "10") (pinfunction "SCL_10") (pintype "input"))
      (node (ref "IC3") (pin "16") (pinfunction "VCC_16") (pintype "power_in"))
      (node (ref "ISP") (pin "2") (pinfunction "2_2") (pintype "passive"))
      (node (ref "PRG") (pin "4") (pinfunction "4_4") (pintype "passive"))
      (node (ref "R1") (pin "1") (pinfunction "1_1") (pintype "passive"))
      (node (ref "TXB0108") (pin "19") (pinfunction "VCCB_19") (pintype "bidirectional"))
      (node (ref "U1") (pin "3") (pinfunction "IN_3") (pintype "input"))
    )
    (net (code "60") (name "12v") (class "Default")
      (node (ref "12V") (pin "1") (pinfunction "1_1") (pintype "passive"))
      (node (ref "COIN") (pin "4") (pinfunction "4_4") (pintype "passive"))
    )
    (net (code "61") (name "24v") (class "Default")
      (node (ref "24V") (pin "1") (pinfunction "1_1") (pintype "passive"))
      (node (ref "C3") (pin "1") (pinfunction "+_1") (pintype "passive"))
      (node (ref "IC4") (pin "1") (pinfunction "K1_1") (pintype "passive"))
      (node (ref "IC4") (pin "8") (pinfunction "K2_8") (pintype "passive"))
      (node (ref "IC5") (pin "1") (pinfunction "K1_1") (pintype "passive"))
      (node (ref "IC5") (pin "8") (pinfunction "K2_8") (pintype "passive"))
      (node (ref "IC6") (pin "1") (pinfunction "K1_1") (pintype "passive"))
      (node (ref "IC6") (pin "8") (pinfunction "K2_8") (pintype "passive"))
      (node (ref "U$2") (pin "1") (pinfunction "VCC1_1") (pintype "bidirectional"))
      (node (ref "U$2") (pin "12") (pinfunction "VCC2_12") (pintype "bidirectional"))
      (node (ref "U$2") (pin "VCC") (pinfunction "VCC3_VCC") (pintype "bidirectional"))
      (node (ref "U$3") (pin "1") (pinfunction "VCC1_1") (pintype "bidirectional"))
      (node (ref "U$3") (pin "12") (pinfunction "VCC2_12") (pintype "bidirectional"))
      (node (ref "U$3") (pin "VCC") (pinfunction "VCC3_VCC") (pintype "bidirectional"))
    )
    (net (code "62") (name "GND") (class "Default")
      (node (ref "BT") (pin "3") (pinfunction "3_3") (pintype "passive"))
      (node (ref "C1") (pin "2") (pinfunction "2_2") (pintype "passive"))
      (node (ref "C10") (pin "2") (pinfunction "2_2") (pintype "passive"))
      (node (ref "C11") (pin "2") (pinfunction "2_2") (pintype "passive"))
      (node (ref "C13") (pin "2") (pinfunction "2_2") (pintype "passive"))
      (node (ref "C14") (pin "2") (pinfunction "2_2") (pintype "passive"))
      (node (ref "C17") (pin "1") (pinfunction "1_1") (pintype "passive"))
      (node (ref "C18") (pin "2") (pinfunction "2_2") (pintype "passive"))
      (node (ref "C19") (pin "2") (pinfunction "2_2") (pintype "passive"))
      (node (ref "C2") (pin "2") (pinfunction "2_2") (pintype "passive"))
      (node (ref "C20") (pin "1") (pinfunction "1_1") (pintype "passive"))
      (node (ref "C21") (pin "2") (pinfunction "2_2") (pintype "passive"))
      (node (ref "C3") (pin "2") (pinfunction "-_2") (pintype "passive"))
      (node (ref "C4") (pin "2") (pinfunction "2_2") (pintype "passive"))
      (node (ref "C7") (pin "2") (pinfunction "2_2") (pintype "passive"))
      (node (ref "C8") (pin "2") (pinfunction "2_2") (pintype "passive"))
      (node (ref "C9") (pin "1") (pinfunction "1_1") (pintype "passive"))
      (node (ref "COIN") (pin "2") (pinfunction "2_2") (pintype "passive"))
      (node (ref "DOOR") (pin "1") (pinfunction "1_1") (pintype "passive"))
      (node (ref "ESP") (pin "2") (pinfunction "2_2") (pintype "passive"))
      (node (ref "GND") (pin "1") (pinfunction "1_1") (pintype "passive"))
      (node (ref "IC1") (pin "18") (pinfunction "GND_18") (pintype "power_in"))
      (node (ref "IC1") (pin "28") (pinfunction "GND_28") (pintype "power_in"))
      (node (ref "IC1") (pin "39") (pinfunction "GND_39") (pintype "power_in"))
      (node (ref "IC1") (pin "6") (pinfunction "GND_6") (pintype "power_in"))
      (node (ref "IC2") (pin "8") (pinfunction "GND_8") (pintype "power_in"))
      (node (ref "IC3") (pin "8") (pinfunction "GND_8") (pintype "power_in"))
      (node (ref "IC4") (pin "12") (pinfunction "GND_12") (pintype "power_in"))
      (node (ref "IC4") (pin "13") (pinfunction "GND_13") (pintype "power_in"))
      (node (ref "IC4") (pin "4") (pinfunction "GND_4") (pintype "power_in"))
      (node (ref "IC4") (pin "5") (pinfunction "GND_5") (pintype "power_in"))
      (node (ref "IC5") (pin "12") (pinfunction "GND_12") (pintype "power_in"))
      (node (ref "IC5") (pin "13") (pinfunction "GND_13") (pintype "power_in"))
      (node (ref "IC5") (pin "4") (pinfunction "GND_4") (pintype "power_in"))
      (node (ref "IC5") (pin "5") (pinfunction "GND_5") (pintype "power_in"))
      (node (ref "IC6") (pin "12") (pinfunction "GND_12") (pintype "power_in"))
      (node (ref "IC6") (pin "13") (pinfunction "GND_13") (pintype "power_in"))
      (node (ref "IC6") (pin "4") (pinfunction "GND_4") (pintype "power_in"))
      (node (ref "IC6") (pin "5") (pinfunction "GND_5") (pintype "power_in"))
      (node (ref "ISP") (pin "6") (pinfunction "6_6") (pintype "passive"))
      (node (ref "NRF") (pin "1") (pinfunction "1_1") (pintype "passive"))
      (node (ref "PRG") (pin "1") (pinfunction "1_1") (pintype "passive"))
      (node (ref "QVGA") (pin "8") (pinfunction "8_8") (pintype "passive"))
      (node (ref "R13") (pin "1") (pinfunction "1_1") (pintype "passive"))
      (node (ref "R14") (pin "1") (pinfunction "1_1") (pintype "passive"))
      (node (ref "R2") (pin "1") (pinfunction "1_1") (pintype "passive"))
      (node (ref "R4") (pin "1") (pinfunction "1_1") (pintype "passive"))
      (node (ref "RFID") (pin "3") (pinfunction "3_3") (pintype "passive"))
      (node (ref "TXB0108") (pin "11") (pinfunction "GND_11") (pintype "bidirectional"))
      (node (ref "U$2") (pin "2") (pinfunction "GND_2") (pintype "bidirectional"))
      (node (ref "U$3") (pin "2") (pinfunction "GND_2") (pintype "bidirectional"))
      (node (ref "U1") (pin "1") (pinfunction "ADJ_1") (pintype "input"))
      (node (ref "Y3") (pin "2") (pinfunction "2_2") (pintype "passive"))
    )
    (net (code "63") (name "Net-(BT-Pad1)") (class "Default")
      (node (ref "BT") (pin "1") (pinfunction "1_1") (pintype "passive"))
      (node (ref "R2") (pin "2") (pinfunction "2_2") (pintype "passive"))
      (node (ref "R3") (pin "1") (pinfunction "1_1") (pintype "passive"))
    )
    (net (code "64") (name "Net-(IC1-XTAL1)") (class "Default")
      (node (ref "IC1") (pin "8") (pinfunction "XTAL1_8") (pintype "bidirectional"))
      (node (ref "Y3") (pin "3") (pinfunction "3_3") (pintype "passive"))
    )
    (net (code "65") (name "Net-(IC1-XTAL2)") (class "Default")
      (node (ref "IC1") (pin "7") (pinfunction "XTAL2_7") (pintype "bidirectional"))
      (node (ref "Y3") (pin "1") (pinfunction "1_1") (pintype "passive"))
    )
    (net (code "66") (name "Net-(IC2-SER)") (class "Default")
      (node (ref "IC2") (pin "14") (pinfunction "SER_14") (pintype "input"))
      (node (ref "IC3") (pin "9") (pinfunction "QH*_9") (pintype "tri_state"))
    )
    (net (code "67") (name "Net-(IC4-O1)") (class "Default")
      (node (ref "IC4") (pin "2") (pinfunction "O1_2") (pintype "open_collector"))
      (node (ref "X1") (pin "7") (pinfunction "1_7") (pintype "passive"))
    )
    (net (code "68") (name "Net-(IC4-O2)") (class "Default")
      (node (ref "IC4") (pin "7") (pinfunction "O2_7") (pintype "open_collector"))
      (node (ref "X1") (pin "8") (pinfunction "1_8") (pintype "passive"))
    )
    (net (code "69") (name "Net-(IC4-O3)") (class "Default")
      (node (ref "IC4") (pin "9") (pinfunction "O3_9") (pintype "open_collector"))
      (node (ref "X2") (pin "1") (pinfunction "1_1") (pintype "passive"))
    )
    (net (code "70") (name "Net-(IC4-O4)") (class "Default")
      (node (ref "IC4") (pin "16") (pinfunction "O4_16") (pintype "open_collector"))
      (node (ref "X2") (pin "2") (pinfunction "1_2") (pintype "passive"))
    )
    (net (code "71") (name "Net-(IC5-O1)") (class "Default")
      (node (ref "IC5") (pin "2") (pinfunction "O1_2") (pintype "open_collector"))
      (node (ref "X2") (pin "3") (pinfunction "1_3") (pintype "passive"))
    )
    (net (code "72") (name "Net-(IC5-O2)") (class "Default")
      (node (ref "IC5") (pin "7") (pinfunction "O2_7") (pintype "open_collector"))
      (node (ref "X2") (pin "4") (pinfunction "1_4") (pintype "passive"))
    )
    (net (code "73") (name "Net-(IC5-O3)") (class "Default")
      (node (ref "IC5") (pin "9") (pinfunction "O3_9") (pintype "open_collector"))
      (node (ref "X2") (pin "5") (pinfunction "1_5") (pintype "passive"))
    )
    (net (code "74") (name "Net-(IC5-O4)") (class "Default")
      (node (ref "IC5") (pin "16") (pinfunction "O4_16") (pintype "open_collector"))
      (node (ref "X2") (pin "6") (pinfunction "1_6") (pintype "passive"))
    )
    (net (code "75") (name "Net-(IC6-O1)") (class "Default")
      (node (ref "IC6") (pin "2") (pinfunction "O1_2") (pintype "open_collector"))
      (node (ref "X2") (pin "7") (pinfunction "1_7") (pintype "passive"))
    )
    (net (code "76") (name "Net-(IC6-O2)") (class "Default")
      (node (ref "IC6") (pin "7") (pinfunction "O2_7") (pintype "open_collector"))
      (node (ref "X2") (pin "8") (pinfunction "1_8") (pintype "passive"))
    )
    (net (code "77") (name "Net-(R4-Pad2)") (class "Default")
      (node (ref "R4") (pin "2") (pinfunction "2_2") (pintype "passive"))
      (node (ref "R5") (pin "1") (pinfunction "1_1") (pintype "passive"))
      (node (ref "RFID") (pin "2") (pinfunction "2_2") (pintype "passive"))
    )
    (net (code "78") (name "Net-(TXB0108-OE)") (class "Default")
      (node (ref "R17") (pin "1") (pinfunction "1_1") (pintype "passive"))
      (node (ref "TXB0108") (pin "10") (pinfunction "OE_10") (pintype "bidirectional"))
    )
    (net (code "79") (name "Net-(U$2-O1_1)") (class "Default")
      (node (ref "U$2") (pin "22") (pinfunction "O1_3_22") (pintype "bidirectional"))
      (node (ref "U$2") (pin "23") (pinfunction "O1_2_23") (pintype "bidirectional"))
      (node (ref "U$2") (pin "24") (pinfunction "O1_1_24") (pintype "bidirectional"))
      (node (ref "X1") (pin "6") (pinfunction "1_6") (pintype "passive"))
    )
    (net (code "80") (name "Net-(U$2-O2_1)") (class "Default")
      (node (ref "U$2") (pin "19") (pinfunction "O2_3_19") (pintype "bidirectional"))
      (node (ref "U$2") (pin "20") (pinfunction "O2_2_20") (pintype "bidirectional"))
      (node (ref "U$2") (pin "21") (pinfunction "O2_1_21") (pintype "bidirectional"))
      (node (ref "X1") (pin "5") (pinfunction "1_5") (pintype "passive"))
    )
    (net (code "81") (name "Net-(U$2-O3_1)") (class "Default")
      (node (ref "U$2") (pin "16") (pinfunction "O3_3_16") (pintype "bidirectional"))
      (node (ref "U$2") (pin "17") (pinfunction "O3_2_17") (pintype "bidirectional"))
      (node (ref "U$2") (pin "18") (pinfunction "O3_1_18") (pintype "bidirectional"))
      (node (ref "X1") (pin "4") (pinfunction "1_4") (pintype "passive"))
    )
    (net (code "82") (name "Net-(U$2-O4_1)") (class "Default")
      (node (ref "U$2") (pin "13") (pinfunction "O4_3_13") (pintype "bidirectional"))
      (node (ref "U$2") (pin "14") (pinfunction "O4_2_14") (pintype "bidirectional"))
      (node (ref "U$2") (pin "15") (pinfunction "O4_1_15") (pintype "bidirectional"))
      (node (ref "X1") (pin "3") (pinfunction "1_3") (pintype "passive"))
    )
    (net (code "83") (name "Net-(U$2-S_DIS)") (class "Default")
      (node (ref "R13") (pin "2") (pinfunction "2_2") (pintype "passive"))
      (node (ref "U$2") (pin "11") (pinfunction "S_DIS_11") (pintype "bidirectional"))
    )
    (net (code "84") (name "Net-(U$3-O1_1)") (class "Default")
      (node (ref "U$3") (pin "22") (pinfunction "O1_3_22") (pintype "bidirectional"))
      (node (ref "U$3") (pin "23") (pinfunction "O1_2_23") (pintype "bidirectional"))
      (node (ref "U$3") (pin "24") (pinfunction "O1_1_24") (pintype "bidirectional"))
      (node (ref "X1") (pin "2") (pinfunction "1_2") (pintype "passive"))
    )
    (net (code "85") (name "Net-(U$3-O2_1)") (class "Default")
      (node (ref "U$3") (pin "19") (pinfunction "O2_3_19") (pintype "bidirectional"))
      (node (ref "U$3") (pin "20") (pinfunction "O2_2_20") (pintype "bidirectional"))
      (node (ref "U$3") (pin "21") (pinfunction "O2_1_21") (pintype "bidirectional"))
      (node (ref "X1") (pin "1") (pinfunction "1_1") (pintype "passive"))
    )
    (net (code "86") (name "Net-(U$3-O3_1)") (class "Default")
      (node (ref "JP1") (pin "1") (pinfunction "1_1") (pintype "passive"))
      (node (ref "U$3") (pin "16") (pinfunction "O3_3_16") (pintype "bidirectional"))
      (node (ref "U$3") (pin "17") (pinfunction "O3_2_17") (pintype "bidirectional"))
      (node (ref "U$3") (pin "18") (pinfunction "O3_1_18") (pintype "bidirectional"))
    )
    (net (code "87") (name "Net-(U$3-O4_1)") (class "Default")
      (node (ref "JP1") (pin "2") (pinfunction "2_2") (pintype "passive"))
      (node (ref "U$3") (pin "13") (pinfunction "O4_3_13") (pintype "bidirectional"))
      (node (ref "U$3") (pin "14") (pinfunction "O4_2_14") (pintype "bidirectional"))
      (node (ref "U$3") (pin "15") (pinfunction "O4_1_15") (pintype "bidirectional"))
    )
    (net (code "88") (name "Net-(U$3-S_DIS)") (class "Default")
      (node (ref "R14") (pin "2") (pinfunction "2_2") (pintype "passive"))
      (node (ref "U$3") (pin "11") (pinfunction "S_DIS_11") (pintype "bidirectional"))
    )
    (net (code "89") (name "unconnected-(COIN-Pad1)") (class "Default")
      (node (ref "COIN") (pin "1") (pinfunction "1_1") (pintype "passive"))
    )
    (net (code "90") (name "unconnected-(ESP-Pad4)") (class "Default")
      (node (ref "ESP") (pin "4") (pinfunction "4_4") (pintype "passive"))
    )
    (net (code "91") (name "unconnected-(ESP-Pad5)") (class "Default")
      (node (ref "ESP") (pin "5") (pinfunction "5_5") (pintype "passive"))
    )
    (net (code "92") (name "unconnected-(ESP-Pad6)") (class "Default")
      (node (ref "ESP") (pin "6") (pinfunction "6_6") (pintype "passive"))
    )
    (net (code "93") (name "unconnected-(IC2-QH*-Pad9)") (class "Default")
      (node (ref "IC2") (pin "9") (pinfunction "QH*_9") (pintype "tri_state"))
    )
    (net (code "94") (name "unconnected-(IC6-I3-Pad11)") (class "Default")
      (node (ref "IC6") (pin "11") (pinfunction "I3_11") (pintype "input"))
    )
    (net (code "95") (name "unconnected-(IC6-I4-Pad14)") (class "Default")
      (node (ref "IC6") (pin "14") (pinfunction "I4_14") (pintype "input"))
    )
    (net (code "96") (name "unconnected-(IC6-O3-Pad9)") (class "Default")
      (node (ref "IC6") (pin "9") (pinfunction "O3_9") (pintype "open_collector"))
    )
    (net (code "97") (name "unconnected-(IC6-O4-Pad16)") (class "Default")
      (node (ref "IC6") (pin "16") (pinfunction "O4_16") (pintype "open_collector"))
    )
    (net (code "98") (name "unconnected-(KPBTM-Pad12)") (class "Default")
      (node (ref "KPBTM") (pin "12") (pinfunction "12_12") (pintype "passive"))
    )
    (net (code "99") (name "unconnected-(KPTOP-Pad2)") (class "Default")
      (node (ref "KPTOP") (pin "2") (pinfunction "2_2") (pintype "passive"))
    )
    (net (code "100") (name "unconnected-(RFID-Pad4)") (class "Default")
      (node (ref "RFID") (pin "4") (pinfunction "4_4") (pintype "passive"))
    )
    (net (code "101") (name "unconnected-(U$2-S1-Pad4)") (class "Default")
      (node (ref "U$2") (pin "4") (pinfunction "S1_4") (pintype "bidirectional"))
    )
    (net (code "102") (name "unconnected-(U$2-S2-Pad6)") (class "Default")
      (node (ref "U$2") (pin "6") (pinfunction "S2_6") (pintype "bidirectional"))
    )
    (net (code "103") (name "unconnected-(U$2-S3-Pad8)") (class "Default")
      (node (ref "U$2") (pin "8") (pinfunction "S3_8") (pintype "bidirectional"))
    )
    (net (code "104") (name "unconnected-(U$2-S4-Pad10)") (class "Default")
      (node (ref "U$2") (pin "10") (pinfunction "S4_10") (pintype "bidirectional"))
    )
    (net (code "105") (name "unconnected-(U$3-I3-Pad7)") (class "Default")
      (node (ref "U$3") (pin "7") (pinfunction "I3_7") (pintype "bidirectional"))
    )
    (net (code "106") (name "unconnected-(U$3-I4-Pad9)") (class "Default")
      (node (ref "U$3") (pin "9") (pinfunction "I4_9") (pintype "bidirectional"))
    )
    (net (code "107") (name "unconnected-(U$3-S1-Pad4)") (class "Default")
      (node (ref "U$3") (pin "4") (pinfunction "S1_4") (pintype "bidirectional"))
    )
    (net (code "108") (name "unconnected-(U$3-S2-Pad6)") (class "Default")
      (node (ref "U$3") (pin "6") (pinfunction "S2_6") (pintype "bidirectional"))
    )
  )
)
